# DDS.net
KiCad netlist of a schematic drawn in Altium Designer
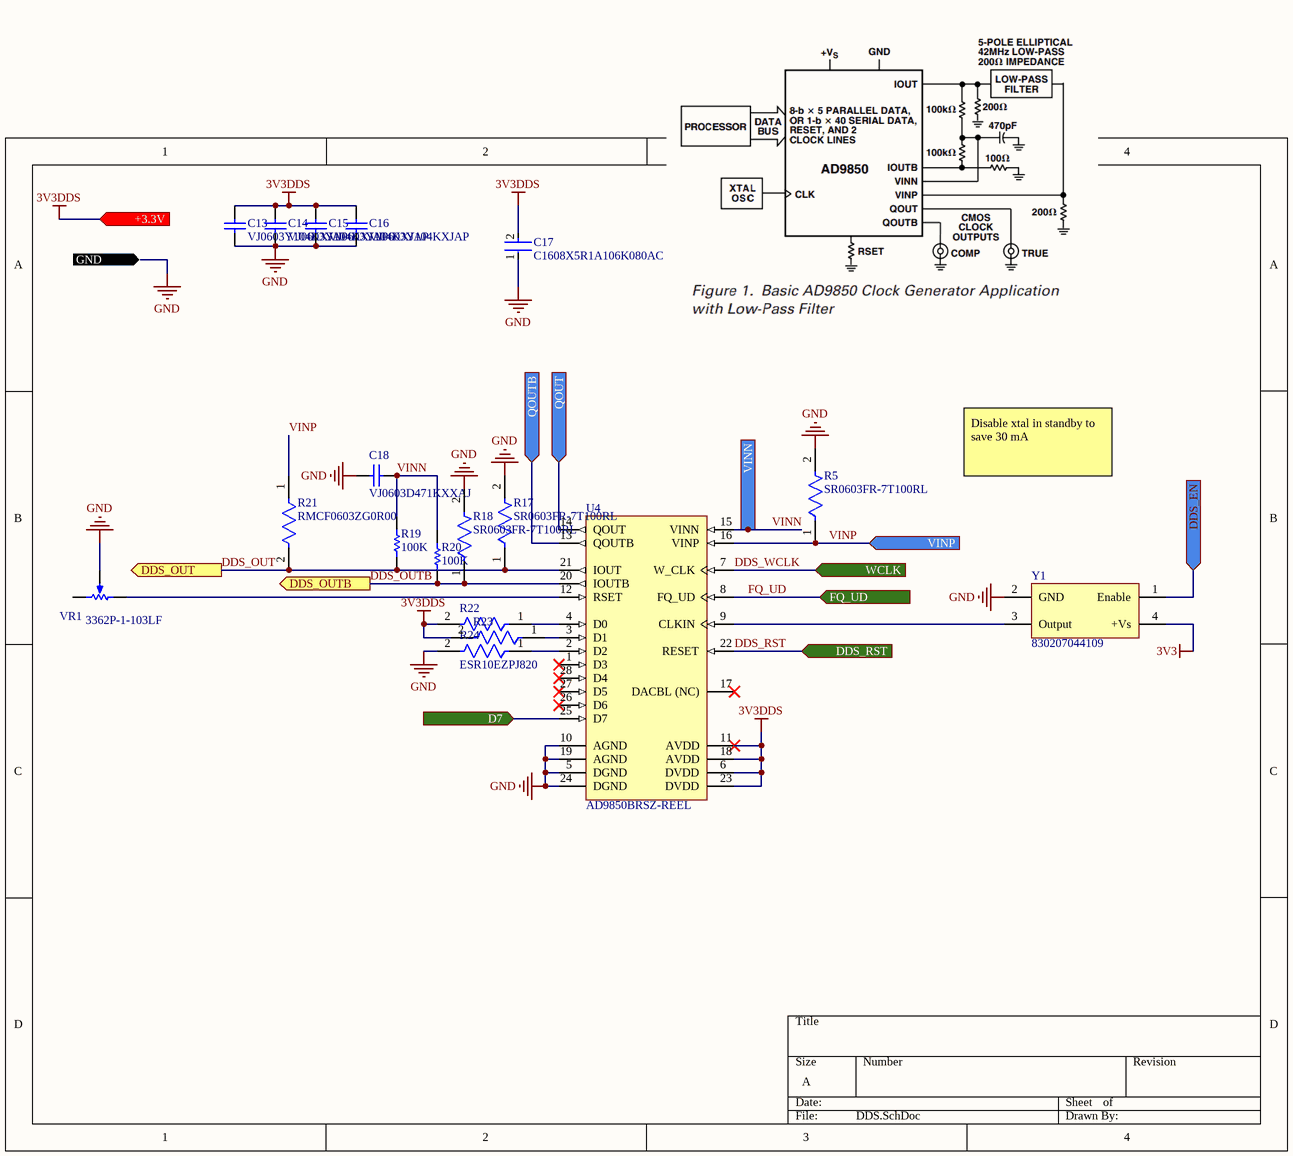
[diagram p0: DDS.SchDoc]

(export (version "E")
  (design (tool "Eeschema 10.0.6"))
  (components
    (comp (ref "C13")
      (value "VJ0603Y104KXJAP")
      (footprint "CAPC1608X92X38NL15T08")
      (fields (field (name "MANUFACTURER") "Vitramon"))
      (libsource (lib "Altium Content Vault") (part "CAP"))
    )
    (comp (ref "C14")
      (value "VJ0603Y104KXJAP")
      (footprint "CAPC1608X92X38NL15T08")
      (fields (field (name "MANUFACTURER") "Vitramon"))
      (libsource (lib "Altium Content Vault") (part "CAP"))
    )
    (comp (ref "C15")
      (value "VJ0603Y104KXJAP")
      (footprint "CAPC1608X92X38NL15T08")
      (fields (field (name "MANUFACTURER") "Vitramon"))
      (libsource (lib "Altium Content Vault") (part "CAP"))
    )
    (comp (ref "C16")
      (value "VJ0603Y104KXJAP")
      (footprint "CAPC1608X92X38NL15T08")
      (fields (field (name "MANUFACTURER") "Vitramon"))
      (libsource (lib "Altium Content Vault") (part "CAP"))
    )
    (comp (ref "C17")
      (value "C1608X5R1A106K080AC")
      (footprint "FP-C1608-080-0_1-MFG")
      (description "Multilayer Ceramic Capacitors 10μF ±10% 10V X5R SMD 0603")
      (fields (field (name "VOLTAGE") "10V") (field (name "TOLERANCE") "10%"))
      (libsource (lib "Altium Content Vault") (part "236180d848d6139a670b325ea6854c9"))
    )
    (comp (ref "C18")
      (value "VJ0603D471KXXAJ")
      (footprint "CAPC1608X92X38LL15T08")
      (fields (field (name "MANUFACTURER") "Vitramon"))
      (libsource (lib "Altium Content Vault") (part "CAP"))
    )
    (comp (ref "R5")
      (value "SR0603FR-7T100RL")
      (footprint "FP-SR0603-MFG")
      (description "SR0603 100Ω 0.25W 1.00%")
      (fields (field (name "MANUFACTURER") "Yageo"))
      (libsource (lib "Altium Content Vault") (part "1029c3af85768c4190bb7ad29bc67b5"))
    )
    (comp (ref "R17")
      (value "SR0603FR-7T100RL")
      (footprint "FP-SR0603-MFG")
      (description "SR0603 100Ω 0.25W 1.00%")
      (fields (field (name "MANUFACTURER") "Yageo"))
      (libsource (lib "Altium Content Vault") (part "1029c3af85768c4190bb7ad29bc67b5"))
    )
    (comp (ref "R18")
      (value "SR0603FR-7T100RL")
      (footprint "FP-SR0603-MFG")
      (description "SR0603 100Ω 0.25W 1.00%")
      (fields (field (name "MANUFACTURER") "Yageo"))
      (libsource (lib "Altium Content Vault") (part "1029c3af85768c4190bb7ad29bc67b5"))
    )
    (comp (ref "R19")
      (value "100K")
      (footprint "RESC0603(1608)_N")
      (description "100K 0.1W 1% 0603 (1608 Metric)  SMD")
      (fields (field (name "POWER") "0.1 W") (field (name "TOLERANCE") "1 %"))
      (libsource (lib "Altium Content Vault") (part "RES"))
    )
    (comp (ref "R20")
      (value "100K")
      (footprint "RESC0603(1608)_N")
      (description "100K 0.1W 1% 0603 (1608 Metric)  SMD")
      (fields (field (name "POWER") "0.1 W") (field (name "TOLERANCE") "1 %"))
      (libsource (lib "Altium Content Vault") (part "RES"))
    )
    (comp (ref "R21")
      (value "RMCF0603ZG0R00")
      (footprint "FP-RMCF0603-IPC_B")
      (description "0Ω ±0 0.1W 0603 Thick Film Chip Resistor AEC-Q200 compliant")
      (libsource (lib "Altium Content Vault") (part "1029c3af85768c4190bb7ad29bc67b5"))
    )
    (comp (ref "R22")
      (value "ESR10EZPJ820")
      (footprint "FP-ESR10-IPC_C")
      (description "82Ω ±5% 0.4W 0805 Anti-Surge Chip Resistor AEC-Q200")
      (fields (field (name "TOLERANCE") "5%"))
      (libsource (lib "Altium Content Vault") (part "1029c3af85768c4190bb7ad29bc67b5"))
    )
    (comp (ref "R23")
      (value "ESR10EZPJ820")
      (footprint "FP-ESR10-IPC_C")
      (description "82Ω ±5% 0.4W 0805 Anti-Surge Chip Resistor AEC-Q200")
      (fields (field (name "TOLERANCE") "5%"))
      (libsource (lib "Altium Content Vault") (part "1029c3af85768c4190bb7ad29bc67b5"))
    )
    (comp (ref "R24")
      (value "ESR10EZPJ820")
      (footprint "FP-ESR10-IPC_C")
      (description "82Ω ±5% 0.4W 0805 Anti-Surge Chip Resistor AEC-Q200")
      (fields (field (name "TOLERANCE") "5%"))
      (libsource (lib "Altium Content Vault") (part "1029c3af85768c4190bb7ad29bc67b5"))
    )
    (comp (ref "U4")
      (value "AD9850BRSZ-REEL")
      (footprint "ADI-RS-28_N")
      (description "CMOS, 125 MHz Complete DDS Synthesizer, 10-Bit, Parallel, Serial, RS-28, 1500 Reel, Pb-Free")
      (libsource (lib "Altium Content Vault") (part "ADI-AD9850-RS-28"))
    )
    (comp (ref "VR1")
      (value "3362P-1-103LF")
      (footprint "BOUR-3362P")
      (description "Square Trimpot(R) Trimming Potentiometer, 10 KOhm, 300 V, -55 to 125 degC, 3-Pin THD, RoHS, Tube")
      (fields (field (name "TOLERANCE") "1%"))
      (libsource (lib "Altium Content Vault") (part "RES-POT-3"))
    )
    (comp (ref "Y1")
      (value "830207044109")
      (footprint "WE-SPXO_CFPS-39")
      (description "830207044109 WE-SPXO Crystal Oscillator")
      (libsource (lib "Altium Content Vault") (part "WE-SPXO_CFPS-39"))
    )
  )
  (nets
    (net (code "1") (name "/D7") (class "Default")
      (node (ref "U4") (pin "25") (pinfunction "D7_25") (pintype "input"))
    )
    (net (code "2") (name "/DDS_EN") (class "Default")
      (node (ref "Y1") (pin "1") (pinfunction "Enable_1") (pintype "passive"))
    )
    (net (code "3") (name "/DDS_OUT") (class "Default")
      (node (ref "R17") (pin "1") (pinfunction "1_1") (pintype "passive"))
      (node (ref "R19") (pin "1") (pinfunction "1_1") (pintype "passive"))
      (node (ref "R21") (pin "2") (pinfunction "2_2") (pintype "passive"))
      (node (ref "U4") (pin "21") (pinfunction "IOUT_21") (pintype "output"))
    )
    (net (code "4") (name "/DDS_OUTB") (class "Default")
      (node (ref "R18") (pin "1") (pinfunction "1_1") (pintype "passive"))
      (node (ref "R20") (pin "1") (pinfunction "1_1") (pintype "passive"))
      (node (ref "U4") (pin "20") (pinfunction "IOUTB_20") (pintype "output"))
    )
    (net (code "5") (name "/DDS_RST") (class "Default")
      (node (ref "U4") (pin "22") (pinfunction "RESET_22") (pintype "input"))
    )
    (net (code "6") (name "/DDS_WCLK") (class "Default")
      (node (ref "U4") (pin "7") (pinfunction "W_CLK_7") (pintype "input"))
    )
    (net (code "7") (name "/FQ_UD") (class "Default")
      (node (ref "U4") (pin "8") (pinfunction "FQ_UD_8") (pintype "input"))
    )
    (net (code "8") (name "/QOUT") (class "Default")
      (node (ref "U4") (pin "14") (pinfunction "QOUT_14") (pintype "output"))
    )
    (net (code "9") (name "/QOUTB") (class "Default")
      (node (ref "U4") (pin "13") (pinfunction "QOUTB_13") (pintype "output"))
    )
    (net (code "10") (name "/VINN") (class "Default")
      (node (ref "C18") (pin "1") (pinfunction "1_1") (pintype "passive"))
      (node (ref "R19") (pin "2") (pinfunction "2_2") (pintype "passive"))
      (node (ref "R20") (pin "2") (pinfunction "2_2") (pintype "passive"))
      (node (ref "U4") (pin "15") (pinfunction "VINN_15") (pintype "input"))
    )
    (net (code "11") (name "/VINP") (class "Default")
      (node (ref "R21") (pin "1") (pinfunction "1_1") (pintype "passive"))
      (node (ref "R5") (pin "1") (pinfunction "1_1") (pintype "passive"))
      (node (ref "U4") (pin "16") (pinfunction "VINP_16") (pintype "input"))
    )
    (net (code "12") (name "3V3") (class "Default")
      (node (ref "Y1") (pin "4") (pinfunction "+Vs_4") (pintype "passive"))
    )
    (net (code "13") (name "3V3DDS") (class "Default")
      (node (ref "C13") (pin "2") (pinfunction "2_2") (pintype "passive"))
      (node (ref "C14") (pin "2") (pinfunction "2_2") (pintype "passive"))
      (node (ref "C15") (pin "2") (pinfunction "2_2") (pintype "passive"))
      (node (ref "C16") (pin "2") (pinfunction "2_2") (pintype "passive"))
      (node (ref "C17") (pin "2") (pinfunction "2_2") (pintype "passive"))
      (node (ref "R22") (pin "2") (pinfunction "2_2") (pintype "passive"))
      (node (ref "R23") (pin "2") (pinfunction "2_2") (pintype "passive"))
      (node (ref "U4") (pin "11") (pinfunction "AVDD_11") (pintype "power_in"))
      (node (ref "U4") (pin "18") (pinfunction "AVDD_18") (pintype "power_in"))
      (node (ref "U4") (pin "23") (pinfunction "DVDD_23") (pintype "power_in"))
      (node (ref "U4") (pin "6") (pinfunction "DVDD_6") (pintype "power_in"))
    )
    (net (code "14") (name "GND") (class "Default")
      (node (ref "C13") (pin "1") (pinfunction "1_1") (pintype "passive"))
      (node (ref "C14") (pin "1") (pinfunction "1_1") (pintype "passive"))
      (node (ref "C15") (pin "1") (pinfunction "1_1") (pintype "passive"))
      (node (ref "C16") (pin "1") (pinfunction "1_1") (pintype "passive"))
      (node (ref "C17") (pin "1") (pinfunction "1_1") (pintype "passive"))
      (node (ref "C18") (pin "2") (pinfunction "2_2") (pintype "passive"))
      (node (ref "R17") (pin "2") (pinfunction "2_2") (pintype "passive"))
      (node (ref "R18") (pin "2") (pinfunction "2_2") (pintype "passive"))
      (node (ref "R24") (pin "2") (pinfunction "2_2") (pintype "passive"))
      (node (ref "R5") (pin "2") (pinfunction "2_2") (pintype "passive"))
      (node (ref "U4") (pin "10") (pinfunction "AGND_10") (pintype "power_in"))
      (node (ref "U4") (pin "19") (pinfunction "AGND_19") (pintype "power_in"))
      (node (ref "U4") (pin "24") (pinfunction "DGND_24") (pintype "power_in"))
      (node (ref "U4") (pin "5") (pinfunction "DGND_5") (pintype "power_in"))
      (node (ref "VR1") (pin "2") (pinfunction "S_2") (pintype "passive"))
      (node (ref "Y1") (pin "2") (pinfunction "GND_2") (pintype "passive"))
    )
    (net (code "15") (name "Net-(U4-CLKIN)") (class "Default")
      (node (ref "U4") (pin "9") (pinfunction "CLKIN_9") (pintype "input"))
      (node (ref "Y1") (pin "3") (pinfunction "Output_3") (pintype "passive"))
    )
    (net (code "16") (name "Net-(U4-D0)") (class "Default")
      (node (ref "R22") (pin "1") (pinfunction "1_1") (pintype "passive"))
      (node (ref "U4") (pin "4") (pinfunction "D0_4") (pintype "input"))
    )
    (net (code "17") (name "Net-(U4-D1)") (class "Default")
      (node (ref "R23") (pin "1") (pinfunction "1_1") (pintype "passive"))
      (node (ref "U4") (pin "3") (pinfunction "D1_3") (pintype "input"))
    )
    (net (code "18") (name "Net-(U4-D2)") (class "Default")
      (node (ref "R24") (pin "1") (pinfunction "1_1") (pintype "passive"))
      (node (ref "U4") (pin "2") (pinfunction "D2_2") (pintype "input"))
    )
    (net (code "19") (name "Net-(U4-RSET)") (class "Default")
      (node (ref "U4") (pin "12") (pinfunction "RSET_12") (pintype "input"))
      (node (ref "VR1") (pin "1") (pinfunction "CCW_1") (pintype "passive"))
    )
    (net (code "20") (name "unconnected-(U4-D3-Pad1)") (class "Default")
      (node (ref "U4") (pin "1") (pinfunction "D3_1") (pintype "input+no_connect"))
    )
    (net (code "21") (name "unconnected-(U4-D4-Pad28)") (class "Default")
      (node (ref "U4") (pin "28") (pinfunction "D4_28") (pintype "input+no_connect"))
    )
    (net (code "22") (name "unconnected-(U4-D5-Pad27)") (class "Default")
      (node (ref "U4") (pin "27") (pinfunction "D5_27") (pintype "input+no_connect"))
    )
    (net (code "23") (name "unconnected-(U4-D6-Pad26)") (class "Default")
      (node (ref "U4") (pin "26") (pinfunction "D6_26") (pintype "input+no_connect"))
    )
    (net (code "24") (name "unconnected-(U4-DACBL_(NC)-Pad17)") (class "Default")
      (node (ref "U4") (pin "17") (pinfunction "DACBL_(NC)_17") (pintype "passive+no_connect"))
    )
    (net (code "25") (name "unconnected-(VR1-CW-Pad3)") (class "Default")
      (node (ref "VR1") (pin "3") (pinfunction "CW_3") (pintype "passive"))
    )
  )
)
